# Sensorboard.net
KiCad netlist of a schematic drawn in EAGLE
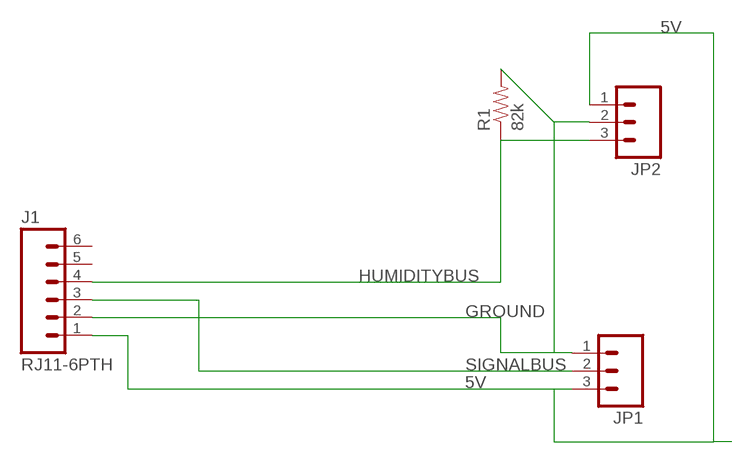
[diagram p0: schematic, sheet 1]

(export (version "E")
  (design (tool "Eeschema 10.0.6"))
  (components
    (comp (ref "J1")
      (value "RJ11-6PTH")
      (footprint "eagle-import:RJ11-6")
      (libsource (lib "eagle-import") (part "RJ11-6PTH"))
    )
    (comp (ref "JP1")
      (value "M03PTH")
      (footprint "eagle-import:1X03")
      (libsource (lib "eagle-import") (part "M03PTH"))
    )
    (comp (ref "JP2")
      (value "M03PTH")
      (footprint "eagle-import:1X03")
      (libsource (lib "eagle-import") (part "M03PTH"))
    )
    (comp (ref "R1")
      (value "82k")
      (footprint "eagle-import:AXIAL-0.3-KIT")
      (libsource (lib "eagle-import") (part "RESISTORKIT"))
    )
  )
  (nets
    (net (code "1") (name "/5V") (class "Default")
      (node (ref "J1") (pin "1") (pinfunction "1_1") (pintype "passive"))
      (node (ref "JP1") (pin "3") (pinfunction "3_3") (pintype "passive"))
      (node (ref "JP2") (pin "1") (pinfunction "1_1") (pintype "passive"))
    )
    (net (code "2") (name "/GROUND") (class "Default")
      (node (ref "J1") (pin "2") (pinfunction "2_2") (pintype "passive"))
      (node (ref "JP1") (pin "1") (pinfunction "1_1") (pintype "passive"))
      (node (ref "JP2") (pin "2") (pinfunction "2_2") (pintype "passive"))
      (node (ref "R1") (pin "P$2") (pinfunction "2_P$2") (pintype "passive"))
    )
    (net (code "3") (name "/HUMIDITYBUS") (class "Default")
      (node (ref "J1") (pin "4") (pinfunction "4_4") (pintype "passive"))
      (node (ref "JP2") (pin "3") (pinfunction "3_3") (pintype "passive"))
      (node (ref "R1") (pin "P$1") (pinfunction "1_P$1") (pintype "passive"))
    )
    (net (code "4") (name "/SIGNALBUS") (class "Default")
      (node (ref "J1") (pin "3") (pinfunction "3_3") (pintype "passive"))
      (node (ref "JP1") (pin "2") (pinfunction "2_2") (pintype "passive"))
    )
    (net (code "5") (name "unconnected-(J1-Pad5)") (class "Default")
      (node (ref "J1") (pin "5") (pinfunction "5_5") (pintype "passive"))
    )
    (net (code "6") (name "unconnected-(J1-Pad6)") (class "Default")
      (node (ref "J1") (pin "6") (pinfunction "6_6") (pintype "passive"))
    )
  )
)
